# 2021-04-27_Coll-Interface.net
KiCad netlist of a schematic drawn in EAGLE
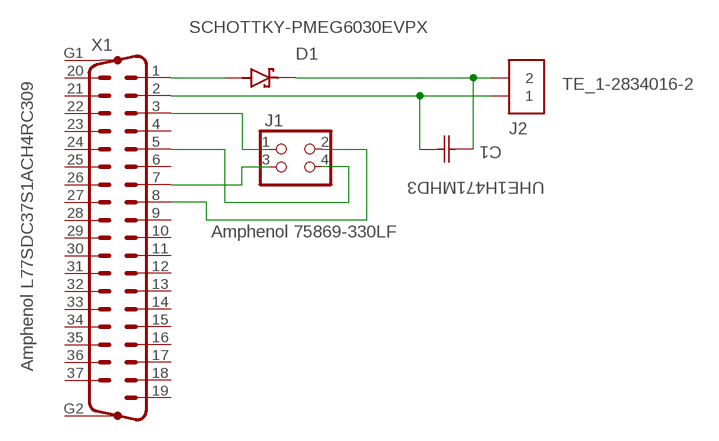
[diagram p0: schematic, sheet 1]

(export (version "E")
  (design (tool "Eeschema 10.0.6"))
  (components
    (comp (ref "C1")
      (value "UHE1H471MHD3")
      (footprint "eagle-import:U1-EE_NCH")
      (libsource (lib "eagle-import") (part "ELECTROLYTIC_UHE1H471MHD3"))
    )
    (comp (ref "D1")
      (value "SCHOTTKY-PMEG6030EVPX")
      (footprint "eagle-import:DIO_PMEG6030EVPX")
      (fields
        (field (name "DIGI-KEY_PART_NUMBER") "1727-1349-1-ND")
        (field (name "MF") "Nexperia USA")
        (field (name "MP") "PMEG6030EVPX")
      )
      (libsource (lib "eagle-import") (part "SCHOTTKY-PMEG6030EVPX"))
    )
    (comp (ref "J1")
      (value "Amphenol 75869-330LF")
      (footprint "eagle-import:2X02-SHROUD")
      (libsource (lib "eagle-import") (part "PINHD-2X2AMP-75869-130LF"))
    )
    (comp (ref "J2")
      (value "TE_1-2834016-2")
      (footprint "eagle-import:TE_1-2834016-2")
      (fields
        (field (name "COMMENT") "1-2834016-2")
        (field (name "DIGI-KEY_PART_NUMBER") "A123829-ND")
        (field (name "MF") "TE Connectivity")
      )
      (libsource (lib "eagle-import") (part "TERMINAL_BLOCK_2PIN_1-2834016-2"))
    )
    (comp (ref "X1")
      (value "Amphenol L77SDC37S1ACH4RC309")
      (footprint "eagle-import:M37HP")
      (libsource (lib "eagle-import") (part "M37HP"))
    )
  )
  (nets
    (net (code "1") (name "Net-(C1-Pad2)") (class "Default")
      (node (ref "C1") (pin "2") (pinfunction "2_2") (pintype "passive"))
      (node (ref "J2") (pin "1.1") (pinfunction "1_1.1") (pintype "passive"))
      (node (ref "J2") (pin "1.2") (pinfunction "1_1.2") (pintype "passive"))
      (node (ref "X1") (pin "2") (pinfunction "2_2") (pintype "passive"))
    )
    (net (code "2") (name "Net-(D1-A)") (class "Default")
      (node (ref "D1") (pin "2") (pinfunction "A_2") (pintype "passive"))
      (node (ref "X1") (pin "1") (pinfunction "1_1") (pintype "passive"))
    )
    (net (code "3") (name "Net-(D1-K)") (class "Default")
      (node (ref "C1") (pin "1") (pinfunction "1_1") (pintype "passive"))
      (node (ref "D1") (pin "1") (pinfunction "K_1") (pintype "passive"))
      (node (ref "J2") (pin "2.1") (pinfunction "2_2.1") (pintype "passive"))
      (node (ref "J2") (pin "2.2") (pinfunction "2_2.2") (pintype "passive"))
    )
    (net (code "4") (name "Net-(J1-Pad1)") (class "Default")
      (node (ref "J1") (pin "1") (pinfunction "1_1") (pintype "passive"))
      (node (ref "X1") (pin "3") (pinfunction "3_3") (pintype "passive"))
    )
    (net (code "5") (name "Net-(J1-Pad2)") (class "Default")
      (node (ref "J1") (pin "2") (pinfunction "2_2") (pintype "passive"))
      (node (ref "X1") (pin "8") (pinfunction "8_8") (pintype "passive"))
    )
    (net (code "6") (name "Net-(J1-Pad3)") (class "Default")
      (node (ref "J1") (pin "3") (pinfunction "3_3") (pintype "passive"))
      (node (ref "X1") (pin "7") (pinfunction "7_7") (pintype "passive"))
    )
    (net (code "7") (name "Net-(J1-Pad4)") (class "Default")
      (node (ref "J1") (pin "4") (pinfunction "4_4") (pintype "passive"))
      (node (ref "X1") (pin "5") (pinfunction "5_5") (pintype "passive"))
    )
    (net (code "8") (name "unconnected-(X1-Pad4)") (class "Default")
      (node (ref "X1") (pin "4") (pinfunction "4_4") (pintype "passive"))
    )
    (net (code "9") (name "unconnected-(X1-Pad6)") (class "Default")
      (node (ref "X1") (pin "6") (pinfunction "6_6") (pintype "passive"))
    )
    (net (code "10") (name "unconnected-(X1-Pad9)") (class "Default")
      (node (ref "X1") (pin "9") (pinfunction "9_9") (pintype "passive"))
    )
    (net (code "11") (name "unconnected-(X1-Pad10)") (class "Default")
      (node (ref "X1") (pin "10") (pinfunction "10_10") (pintype "passive"))
    )
    (net (code "12") (name "unconnected-(X1-Pad11)") (class "Default")
      (node (ref "X1") (pin "11") (pinfunction "11_11") (pintype "passive"))
    )
    (net (code "13") (name "unconnected-(X1-Pad12)") (class "Default")
      (node (ref "X1") (pin "12") (pinfunction "12_12") (pintype "passive"))
    )
    (net (code "14") (name "unconnected-(X1-Pad13)") (class "Default")
      (node (ref "X1") (pin "13") (pinfunction "13_13") (pintype "passive"))
    )
    (net (code "15") (name "unconnected-(X1-Pad14)") (class "Default")
      (node (ref "X1") (pin "14") (pinfunction "14_14") (pintype "passive"))
    )
    (net (code "16") (name "unconnected-(X1-Pad15)") (class "Default")
      (node (ref "X1") (pin "15") (pinfunction "15_15") (pintype "passive"))
    )
    (net (code "17") (name "unconnected-(X1-Pad16)") (class "Default")
      (node (ref "X1") (pin "16") (pinfunction "16_16") (pintype "passive"))
    )
    (net (code "18") (name "unconnected-(X1-Pad17)") (class "Default")
      (node (ref "X1") (pin "17") (pinfunction "17_17") (pintype "passive"))
    )
    (net (code "19") (name "unconnected-(X1-Pad18)") (class "Default")
      (node (ref "X1") (pin "18") (pinfunction "18_18") (pintype "passive"))
    )
    (net (code "20") (name "unconnected-(X1-Pad19)") (class "Default")
      (node (ref "X1") (pin "19") (pinfunction "19_19") (pintype "passive"))
    )
    (net (code "21") (name "unconnected-(X1-Pad20)") (class "Default")
      (node (ref "X1") (pin "20") (pinfunction "20_20") (pintype "passive"))
    )
    (net (code "22") (name "unconnected-(X1-Pad21)") (class "Default")
      (node (ref "X1") (pin "21") (pinfunction "21_21") (pintype "passive"))
    )
    (net (code "23") (name "unconnected-(X1-Pad22)") (class "Default")
      (node (ref "X1") (pin "22") (pinfunction "22_22") (pintype "passive"))
    )
    (net (code "24") (name "unconnected-(X1-Pad23)") (class "Default")
      (node (ref "X1") (pin "23") (pinfunction "23_23") (pintype "passive"))
    )
    (net (code "25") (name "unconnected-(X1-Pad24)") (class "Default")
      (node (ref "X1") (pin "24") (pinfunction "24_24") (pintype "passive"))
    )
    (net (code "26") (name "unconnected-(X1-Pad25)") (class "Default")
      (node (ref "X1") (pin "25") (pinfunction "25_25") (pintype "passive"))
    )
    (net (code "27") (name "unconnected-(X1-Pad26)") (class "Default")
      (node (ref "X1") (pin "26") (pinfunction "26_26") (pintype "passive"))
    )
    (net (code "28") (name "unconnected-(X1-Pad27)") (class "Default")
      (node (ref "X1") (pin "27") (pinfunction "27_27") (pintype "passive"))
    )
    (net (code "29") (name "unconnected-(X1-Pad28)") (class "Default")
      (node (ref "X1") (pin "28") (pinfunction "28_28") (pintype "passive"))
    )
    (net (code "30") (name "unconnected-(X1-Pad29)") (class "Default")
      (node (ref "X1") (pin "29") (pinfunction "29_29") (pintype "passive"))
    )
    (net (code "31") (name "unconnected-(X1-Pad30)") (class "Default")
      (node (ref "X1") (pin "30") (pinfunction "30_30") (pintype "passive"))
    )
    (net (code "32") (name "unconnected-(X1-Pad31)") (class "Default")
      (node (ref "X1") (pin "31") (pinfunction "31_31") (pintype "passive"))
    )
    (net (code "33") (name "unconnected-(X1-Pad32)") (class "Default")
      (node (ref "X1") (pin "32") (pinfunction "32_32") (pintype "passive"))
    )
    (net (code "34") (name "unconnected-(X1-Pad33)") (class "Default")
      (node (ref "X1") (pin "33") (pinfunction "33_33") (pintype "passive"))
    )
    (net (code "35") (name "unconnected-(X1-Pad34)") (class "Default")
      (node (ref "X1") (pin "34") (pinfunction "34_34") (pintype "passive"))
    )
    (net (code "36") (name "unconnected-(X1-Pad35)") (class "Default")
      (node (ref "X1") (pin "35") (pinfunction "35_35") (pintype "passive"))
    )
    (net (code "37") (name "unconnected-(X1-Pad36)") (class "Default")
      (node (ref "X1") (pin "36") (pinfunction "36_36") (pintype "passive"))
    )
    (net (code "38") (name "unconnected-(X1-Pad37)") (class "Default")
      (node (ref "X1") (pin "37") (pinfunction "37_37") (pintype "passive"))
    )
    (net (code "39") (name "unconnected-(X1-PadG1)") (class "Default")
      (node (ref "X1") (pin "G1") (pinfunction "G1_G1") (pintype "passive"))
    )
    (net (code "40") (name "unconnected-(X1-PadG2)") (class "Default")
      (node (ref "X1") (pin "G2") (pinfunction "G2_G2") (pintype "passive"))
    )
  )
)
